# Motor_Driver.net
KiCad netlist of a schematic drawn in Altium Designer
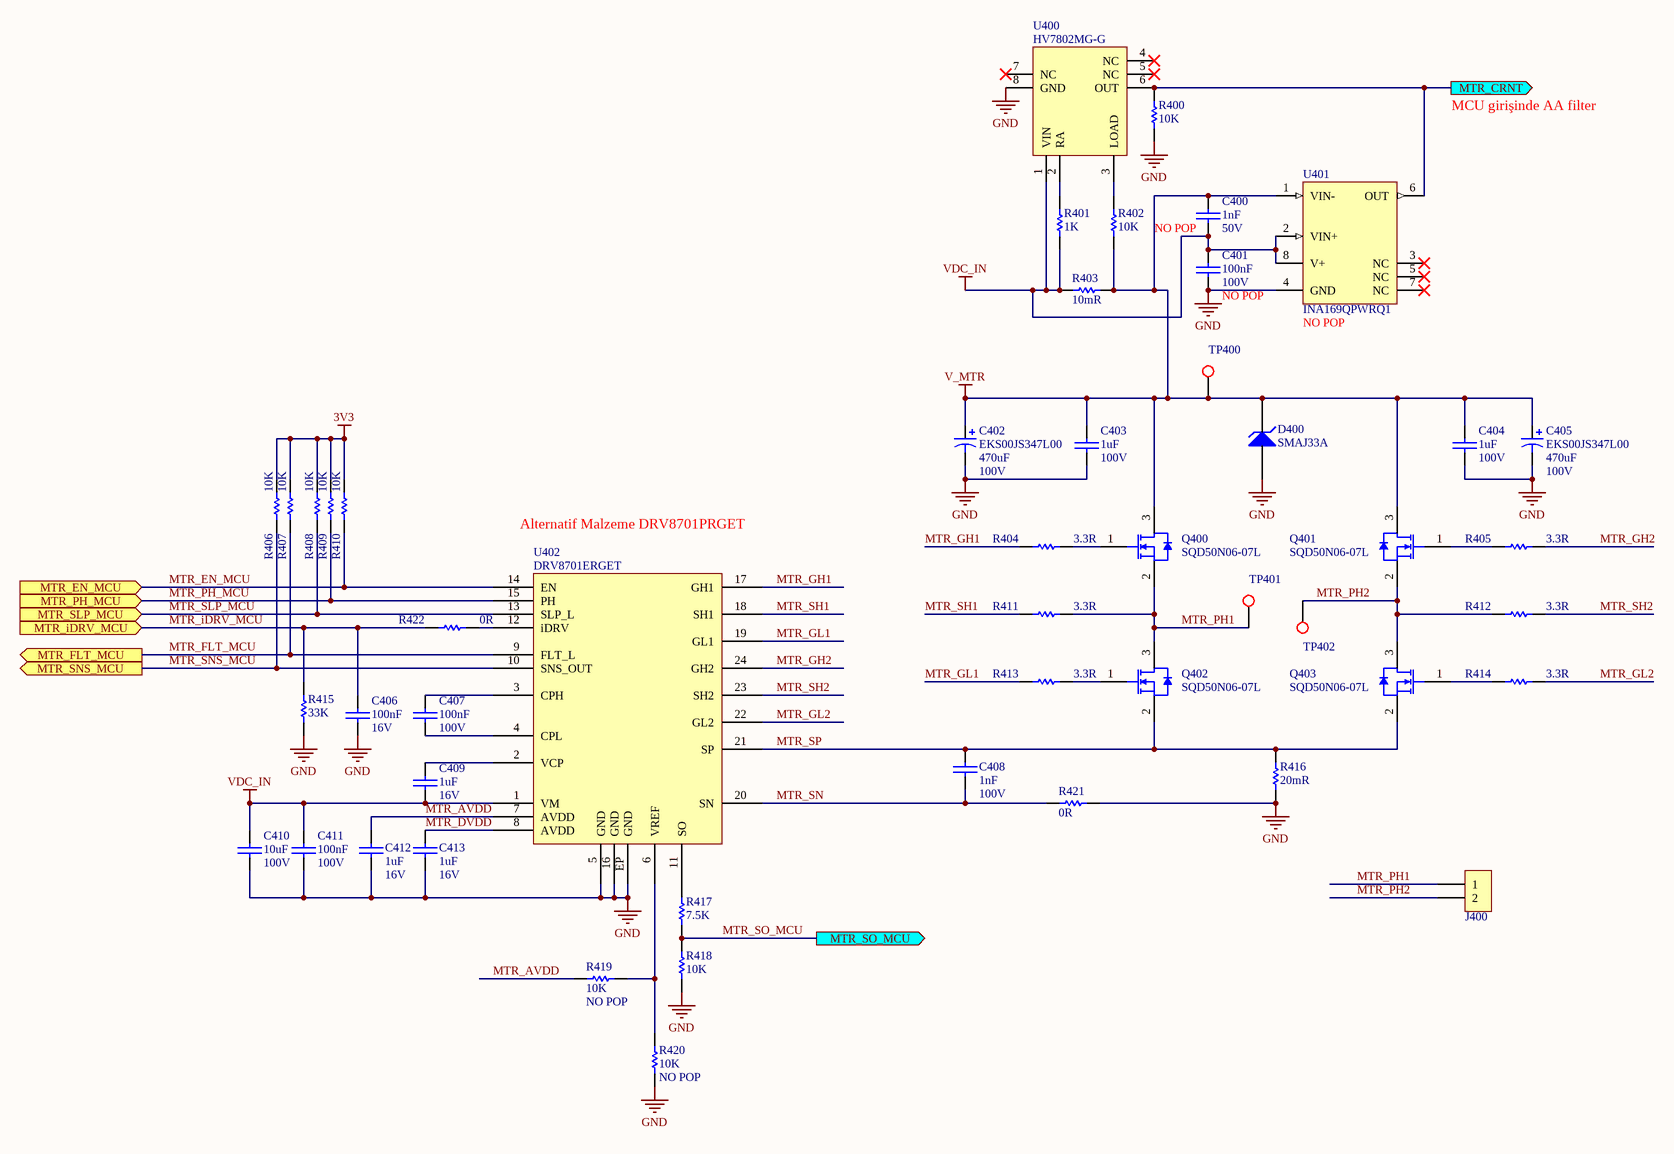
[diagram p0: Motor_Driver.SchDoc]

(export (version "E")
  (design (tool "Eeschema 10.0.6"))
  (components
    (comp (ref "C400")
      (value "1nF")
      (footprint "CAPC1005X06N")
      (description "CAP, CER, C0G, 1nF, %5, 50V, 0402")
      (fields
        (field (name "MANUFACTURER") "Murata")
        (field (name "MANUFACTURER PART NUMBER") "GRM1555C1H102JA01D")
        (field (name "OPERATING VOLTAGE") "50V")
        (field (name "ASSEMBLY") "NO POP")
      )
      (libsource (lib "Anime_Capacitor") (part "ACC0-0100-S272-0000"))
    )
    (comp (ref "C401")
      (value "100nF")
      (footprint "CAPC3216X09N")
      (description "CAP, CER, X7R, 100nF, %10, 100V, 1206")
      (fields
        (field (name "MANUFACTURER") "KEMET")
        (field (name "MANUFACTURER PART NUMBER") "C1206C104K1RACTU")
        (field (name "OPERATING VOLTAGE") "100V")
        (field (name "ASSEMBLY") "NO POP")
      )
      (libsource (lib "Anime_Capacitor") (part "ACC7-2100-S791-0000"))
    )
    (comp (ref "C402")
      (value "EKS00JS347L00")
      (footprint "CAPPR7.5-16X31.5")
      (description "Aluminum Electrolytic Capacitor, Radial Style with Long Leads: 470uF, 100V")
      (fields
        (field (name "ALTIUM_VALUE") "470uF")
        (field (name "RATED VOLTAGE") "100V")
        (field (name "PUBLISHER") "Altium Limited")
      )
      (libsource (lib "Vishay Roederstein Electrolytic Radial-Lead Capacitor") (part "EKS00JS347L00"))
    )
    (comp (ref "C403")
      (value "1uF")
      (footprint "CAPC3216X09N")
      (description "CAP, CER, X7R, 1uF, %10, 100V, 1206")
      (fields
        (field (name "MANUFACTURER") "Murata")
        (field (name "MANUFACTURER PART NUMBER") "GRM31CR72A105KA01L")
        (field (name "OPERATING VOLTAGE") "100V")
      )
      (libsource (lib "Anime_Capacitor") (part "ACC7-3100-S691-0000"))
    )
    (comp (ref "C404")
      (value "1uF")
      (footprint "CAPC3216X09N")
      (description "CAP, CER, X7R, 1uF, %10, 100V, 1206")
      (fields
        (field (name "MANUFACTURER") "Murata")
        (field (name "MANUFACTURER PART NUMBER") "GRM31CR72A105KA01L")
        (field (name "OPERATING VOLTAGE") "100V")
      )
      (libsource (lib "Anime_Capacitor") (part "ACC7-3100-S691-0000"))
    )
    (comp (ref "C405")
      (value "EKS00JS347L00")
      (footprint "CAPPR7.5-16X31.5")
      (description "Aluminum Electrolytic Capacitor, Radial Style with Long Leads: 470uF, 100V")
      (fields
        (field (name "ALTIUM_VALUE") "470uF")
        (field (name "RATED VOLTAGE") "100V")
        (field (name "PUBLISHER") "Altium Limited")
      )
      (libsource (lib "Vishay Roederstein Electrolytic Radial-Lead Capacitor") (part "EKS00JS347L00"))
    )
    (comp (ref "C406")
      (value "100nF")
      (footprint "CAPC1005X06N")
      (description "CAP, CER, X7R, 100nF, %10, 16V, 0402")
      (fields
        (field (name "MANUFACTURER") "Murata")
        (field (name "MANUFACTURER PART NUMBER") "GRM155R71C104KA88D")
        (field (name "OPERATING VOLTAGE") "16V")
      )
      (libsource (lib "Anime_Capacitor") (part "ACC7-2100-S241-0000"))
    )
    (comp (ref "C407")
      (value "100nF")
      (footprint "CAPC3216X09N")
      (description "CAP, CER, X7R, 100nF, %10, 100V, 1206")
      (fields
        (field (name "MANUFACTURER") "KEMET")
        (field (name "MANUFACTURER PART NUMBER") "C1206C104K1RACTU")
        (field (name "OPERATING VOLTAGE") "100V")
      )
      (libsource (lib "Anime_Capacitor") (part "ACC7-2100-S791-0000"))
    )
    (comp (ref "C408")
      (value "1nF")
      (footprint "CAPC1608X09N")
      (description "CAP, CER, X7R, 1nF, %10, 100V, 0603")
      (fields
        (field (name "MANUFACTURER") "Murata")
        (field (name "MANUFACTURER PART NUMBER") "GRM188R72A102KA01D")
        (field (name "OPERATING VOLTAGE") "100V")
      )
      (libsource (lib "Anime_Capacitor") (part "ACC7-0100-S391-0000"))
    )
    (comp (ref "C409")
      (value "1uF")
      (footprint "CAPC2012X14N")
      (description "CAP, CER, X7R, 1uF, %10, 16V, 0805")
      (fields
        (field (name "MANUFACTURER") "Murata")
        (field (name "MANUFACTURER PART NUMBER") "GRM21BR71C105KA01L")
        (field (name "OPERATING VOLTAGE") "16V")
      )
      (libsource (lib "Anime_Capacitor") (part "ACC7-3100-S441-0000"))
    )
    (comp (ref "C410")
      (value "10uF")
      (footprint "CAPC5750X25N")
      (description "CAP, CER, X7S, 10uF, %10, 100V, 2220")
      (fields
        (field (name "MANUFACTURER") "TDK")
        (field (name "MANUFACTURER PART NUMBER") "CGA9N3X7S2A106K230KB")
        (field (name "OPERATING VOLTAGE") "100V")
      )
      (libsource (lib "Anime_Capacitor") (part "ACC4-4100-SD91-0000"))
    )
    (comp (ref "C411")
      (value "100nF")
      (footprint "CAPC3216X09N")
      (description "CAP, CER, X7R, 100nF, %10, 100V, 1206")
      (fields
        (field (name "MANUFACTURER") "KEMET")
        (field (name "MANUFACTURER PART NUMBER") "C1206C104K1RACTU")
        (field (name "OPERATING VOLTAGE") "100V")
      )
      (libsource (lib "Anime_Capacitor") (part "ACC7-2100-S791-0000"))
    )
    (comp (ref "C412")
      (value "1uF")
      (footprint "CAPC2012X14N")
      (description "CAP, CER, X7R, 1uF, %10, 16V, 0805")
      (fields
        (field (name "MANUFACTURER") "Murata")
        (field (name "MANUFACTURER PART NUMBER") "GRM21BR71C105KA01L")
        (field (name "OPERATING VOLTAGE") "16V")
      )
      (libsource (lib "Anime_Capacitor") (part "ACC7-3100-S441-0000"))
    )
    (comp (ref "C413")
      (value "1uF")
      (footprint "CAPC2012X14N")
      (description "CAP, CER, X7R, 1uF, %10, 16V, 0805")
      (fields
        (field (name "MANUFACTURER") "Murata")
        (field (name "MANUFACTURER PART NUMBER") "GRM21BR71C105KA01L")
        (field (name "OPERATING VOLTAGE") "16V")
      )
      (libsource (lib "Anime_Capacitor") (part "ACC7-3100-S441-0000"))
    )
    (comp (ref "D400")
      (value "SMAJ33A")
      (footprint "DIOM5226X23N")
      (description "Diode, TVS, 3.5V @35A, 33V, 400W,  Uni-directional, DO-214AC")
      (fields (field (name "MANUFACTURER PART NUMBER") "SMAJ33A-13-F") (field (name "MANUFACTURER") "Diodes"))
      (libsource (lib "Anime_Semiconductor") (part "AS1H-975M-SI60-0001"))
    )
    (comp (ref "J400")
      (value "~")
      (footprint "AJ61-1002-TAPR-RNS0")
      (description "CON, Terminal, Klemens, 2 Pins, 1-Row, 5.08mm, TH, P, R")
      (fields
        (field (name "MANUFACTURER") "ON-SHORE")
        (field (name "MANUFACTURER PART NUMBER") "OSTOQ025451")
      )
      (libsource (lib "Anime_Connector") (part "AJ61-1002-TAPR-RNS0"))
    )
    (comp (ref "Q400")
      (value "SQD50N06-07L")
      (footprint "TO228P970-3N")
      (description "Transistor, MOSFET, N, 60V, 50A, 7.6mR, SQD50N06-07L, TO-252")
      (fields
        (field (name "MANUFACTURER PART NUMBER") "SQD50N06-07L-GE3")
        (field (name "MANUFACTURER") "VISHAY")
      )
      (libsource (lib "Anime_Semiconductor") (part "AS26-A50M-SI40-0000"))
    )
    (comp (ref "Q401")
      (value "SQD50N06-07L")
      (footprint "TO228P970-3N")
      (description "Transistor, MOSFET, N, 60V, 50A, 7.6mR, SQD50N06-07L, TO-252")
      (fields
        (field (name "MANUFACTURER PART NUMBER") "SQD50N06-07L-GE3")
        (field (name "MANUFACTURER") "VISHAY")
      )
      (libsource (lib "Anime_Semiconductor") (part "AS26-A50M-SI40-0000"))
    )
    (comp (ref "Q402")
      (value "SQD50N06-07L")
      (footprint "TO228P970-3N")
      (description "Transistor, MOSFET, N, 60V, 50A, 7.6mR, SQD50N06-07L, TO-252")
      (fields
        (field (name "MANUFACTURER PART NUMBER") "SQD50N06-07L-GE3")
        (field (name "MANUFACTURER") "VISHAY")
      )
      (libsource (lib "Anime_Semiconductor") (part "AS26-A50M-SI40-0000"))
    )
    (comp (ref "Q403")
      (value "SQD50N06-07L")
      (footprint "TO228P970-3N")
      (description "Transistor, MOSFET, N, 60V, 50A, 7.6mR, SQD50N06-07L, TO-252")
      (fields
        (field (name "MANUFACTURER PART NUMBER") "SQD50N06-07L-GE3")
        (field (name "MANUFACTURER") "VISHAY")
      )
      (libsource (lib "Anime_Semiconductor") (part "AS26-A50M-SI40-0000"))
    )
    (comp (ref "R400")
      (value "10K")
      (footprint "RESC1005X04N")
      (description "RES, E24, Thick Film, SMD, 10K, 1%, 0.1W, 0402")
      (fields
        (field (name "MANUFACTURER") "Panasonic")
        (field (name "MANUFACTURER PART NUMBER") "ERJ-2RKF1002X")
      )
      (libsource (lib "Anime_Resistor") (part "AR19-4100-S2B2-0000"))
    )
    (comp (ref "R401")
      (value "1K")
      (footprint "RESC1005X04N")
      (description "RES, E24, Thick Film, SMD, 1K, 1%, 0.1W, 0402")
      (fields
        (field (name "MANUFACTURER") "Panasonic")
        (field (name "MANUFACTURER PART NUMBER") "ERJ-2RKF1001X")
      )
      (libsource (lib "Anime_Resistor") (part "AR19-3100-S2B2-0000"))
    )
    (comp (ref "R402")
      (value "10K")
      (footprint "RESC1005X04N")
      (description "RES, E24, Thick Film, SMD, 10K, 1%, 0.1W, 0402")
      (fields
        (field (name "MANUFACTURER") "Panasonic")
        (field (name "MANUFACTURER PART NUMBER") "ERJ-2RKF1002X")
      )
      (libsource (lib "Anime_Resistor") (part "AR19-4100-S2B2-0000"))
    )
    (comp (ref "R403")
      (value "10mR")
      (footprint "RESC3216X08N")
      (description "RES, Thick Film, SMD, 10mR, 1%, 1W, 1206")
      (fields
        (field (name "MANUFACTURER") "Panasonic")
        (field (name "MANUFACTURER PART NUMBER") "ERJ-8BWFR010V")
      )
      (libsource (lib "Anime_Resistor") (part "AR19-Y100-S5D2-0000"))
    )
    (comp (ref "R404")
      (value "3.3R")
      (footprint "RESC2012X07N")
      (description "RES, E24, Thick Film, SMD, 3.3R, 1%, 0.125W, 0805")
      (fields
        (field (name "MANUFACTURER") "Panasonic")
        (field (name "MANUFACTURER PART NUMBER") "ERJ-6RQF3R3V")
      )
      (libsource (lib "Anime_Resistor") (part "AR19-0330-S4D2-0000"))
    )
    (comp (ref "R405")
      (value "3.3R")
      (footprint "RESC2012X07N")
      (description "RES, E24, Thick Film, SMD, 3.3R, 1%, 0.125W, 0805")
      (fields
        (field (name "MANUFACTURER") "Panasonic")
        (field (name "MANUFACTURER PART NUMBER") "ERJ-6RQF3R3V")
      )
      (libsource (lib "Anime_Resistor") (part "AR19-0330-S4D2-0000"))
    )
    (comp (ref "R406")
      (value "10K")
      (footprint "RESC1005X04N")
      (description "RES, E24, Thick Film, SMD, 10K, 1%, 0.1W, 0402")
      (fields
        (field (name "MANUFACTURER") "Panasonic")
        (field (name "MANUFACTURER PART NUMBER") "ERJ-2RKF1002X")
      )
      (libsource (lib "Anime_Resistor") (part "AR19-4100-S2B2-0000"))
    )
    (comp (ref "R407")
      (value "10K")
      (footprint "RESC1005X04N")
      (description "RES, E24, Thick Film, SMD, 10K, 1%, 0.1W, 0402")
      (fields
        (field (name "MANUFACTURER") "Panasonic")
        (field (name "MANUFACTURER PART NUMBER") "ERJ-2RKF1002X")
      )
      (libsource (lib "Anime_Resistor") (part "AR19-4100-S2B2-0000"))
    )
    (comp (ref "R408")
      (value "10K")
      (footprint "RESC1005X04N")
      (description "RES, E24, Thick Film, SMD, 10K, 1%, 0.1W, 0402")
      (fields
        (field (name "MANUFACTURER") "Panasonic")
        (field (name "MANUFACTURER PART NUMBER") "ERJ-2RKF1002X")
      )
      (libsource (lib "Anime_Resistor") (part "AR19-4100-S2B2-0000"))
    )
    (comp (ref "R409")
      (value "10K")
      (footprint "RESC1005X04N")
      (description "RES, E24, Thick Film, SMD, 10K, 1%, 0.1W, 0402")
      (fields
        (field (name "MANUFACTURER") "Panasonic")
        (field (name "MANUFACTURER PART NUMBER") "ERJ-2RKF1002X")
      )
      (libsource (lib "Anime_Resistor") (part "AR19-4100-S2B2-0000"))
    )
    (comp (ref "R410")
      (value "10K")
      (footprint "RESC1005X04N")
      (description "RES, E24, Thick Film, SMD, 10K, 1%, 0.1W, 0402")
      (fields
        (field (name "MANUFACTURER") "Panasonic")
        (field (name "MANUFACTURER PART NUMBER") "ERJ-2RKF1002X")
      )
      (libsource (lib "Anime_Resistor") (part "AR19-4100-S2B2-0000"))
    )
    (comp (ref "R411")
      (value "3.3R")
      (footprint "RESC2012X07N")
      (description "RES, E24, Thick Film, SMD, 3.3R, 1%, 0.125W, 0805")
      (fields
        (field (name "MANUFACTURER") "Panasonic")
        (field (name "MANUFACTURER PART NUMBER") "ERJ-6RQF3R3V")
      )
      (libsource (lib "Anime_Resistor") (part "AR19-0330-S4D2-0000"))
    )
    (comp (ref "R412")
      (value "3.3R")
      (footprint "RESC2012X07N")
      (description "RES, E24, Thick Film, SMD, 3.3R, 1%, 0.125W, 0805")
      (fields
        (field (name "MANUFACTURER") "Panasonic")
        (field (name "MANUFACTURER PART NUMBER") "ERJ-6RQF3R3V")
      )
      (libsource (lib "Anime_Resistor") (part "AR19-0330-S4D2-0000"))
    )
    (comp (ref "R413")
      (value "3.3R")
      (footprint "RESC2012X07N")
      (description "RES, E24, Thick Film, SMD, 3.3R, 1%, 0.125W, 0805")
      (fields
        (field (name "MANUFACTURER") "Panasonic")
        (field (name "MANUFACTURER PART NUMBER") "ERJ-6RQF3R3V")
      )
      (libsource (lib "Anime_Resistor") (part "AR19-0330-S4D2-0000"))
    )
    (comp (ref "R414")
      (value "3.3R")
      (footprint "RESC2012X07N")
      (description "RES, E24, Thick Film, SMD, 3.3R, 1%, 0.125W, 0805")
      (fields
        (field (name "MANUFACTURER") "Panasonic")
        (field (name "MANUFACTURER PART NUMBER") "ERJ-6RQF3R3V")
      )
      (libsource (lib "Anime_Resistor") (part "AR19-0330-S4D2-0000"))
    )
    (comp (ref "R415")
      (value "33K")
      (footprint "RESC1005X04N")
      (description "RES, E24, Thick Film, SMD, 33K, 1%, 0.1W, 0402")
      (fields
        (field (name "MANUFACTURER") "Panasonic")
        (field (name "MANUFACTURER PART NUMBER") "ERJ-2RKF3302X")
      )
      (libsource (lib "Anime_Resistor") (part "AR19-4330-S2B2-0000"))
    )
    (comp (ref "R416")
      (value "20mR")
      (footprint "RESC3216X08N")
      (description "RES, Thick Film, SMD, 20mR, 1%, 1W, 1206")
      (fields
        (field (name "MANUFACTURER") "Panasonic")
        (field (name "MANUFACTURER PART NUMBER") "ERJ-8BWFR020V")
      )
      (libsource (lib "Anime_Resistor") (part "AR19-Y200-S5D2-0000"))
    )
    (comp (ref "R417")
      (value "7.5K")
      (footprint "RESC1005X04N")
      (description "RES, E24, Thick Film, SMD, 7.5K, 1%, 0.1W, 0402")
      (fields
        (field (name "MANUFACTURER") "Panasonic")
        (field (name "MANUFACTURER PART NUMBER") "ERJ-2RKF7501X")
      )
      (libsource (lib "Anime_Resistor") (part "AR19-3750-S2B2-0000"))
    )
    (comp (ref "R418")
      (value "10K")
      (footprint "RESC1005X04N")
      (description "RES, E24, Thick Film, SMD, 10K, 1%, 0.1W, 0402")
      (fields
        (field (name "MANUFACTURER") "Panasonic")
        (field (name "MANUFACTURER PART NUMBER") "ERJ-2RKF1002X")
      )
      (libsource (lib "Anime_Resistor") (part "AR19-4100-S2B2-0000"))
    )
    (comp (ref "R419")
      (value "10K")
      (footprint "RESC1005X04N")
      (description "RES, E24, Thick Film, SMD, 10K, 1%, 0.1W, 0402")
      (fields
        (field (name "MANUFACTURER") "Panasonic")
        (field (name "MANUFACTURER PART NUMBER") "ERJ-2RKF1002X")
        (field (name "ASSEMBLY") "NO POP")
      )
      (libsource (lib "Anime_Resistor") (part "AR19-4100-S2B2-0000"))
    )
    (comp (ref "R420")
      (value "10K")
      (footprint "RESC1005X04N")
      (description "RES, E24, Thick Film, SMD, 10K, 1%, 0.1W, 0402")
      (fields
        (field (name "MANUFACTURER") "Panasonic")
        (field (name "MANUFACTURER PART NUMBER") "ERJ-2RKF1002X")
        (field (name "ASSEMBLY") "NO POP")
      )
      (libsource (lib "Anime_Resistor") (part "AR19-4100-S2B2-0000"))
    )
    (comp (ref "R421")
      (value "0R")
      (footprint "RESC2012X07N")
      (description "RES, Thick Film, SMD, 0R, Jumper, 0.125W, 0805")
      (fields
        (field (name "MANUFACTURER") "Panasonic")
        (field (name "MANUFACTURER PART NUMBER") "ERJ-6GEY0R00V")
      )
      (libsource (lib "Anime_Resistor") (part "AR19-0000-S407-0000"))
    )
    (comp (ref "R422")
      (value "0R")
      (footprint "RESC1005X04N")
      (description "RES, Thick Film, SMD, 0R, Jumper, 0.1W, 0402")
      (fields
        (field (name "MANUFACTURER") "Panasonic")
        (field (name "MANUFACTURER PART NUMBER") "ERJ-2GE0R00X")
      )
      (libsource (lib "Anime_Resistor") (part "AR19-0000-S201-0000"))
    )
    (comp (ref "TP400")
      (value "AEMT-C00S-1000-0000")
      (footprint "TP100")
      (description "Test Point, Circular, 1mm")
      (libsource (lib "Anime_Electromechanical") (part "AEMT-C00S-1000-0000"))
    )
    (comp (ref "TP401")
      (value "AEMT-C00S-1000-0000")
      (footprint "TP100")
      (description "Test Point, Circular, 1mm")
      (libsource (lib "Anime_Electromechanical") (part "AEMT-C00S-1000-0000"))
    )
    (comp (ref "TP402")
      (value "AEMT-C00S-1000-0000")
      (footprint "TP100")
      (description "Test Point, Circular, 1mm")
      (libsource (lib "Anime_Electromechanical") (part "AEMT-C00S-1000-0000"))
    )
    (comp (ref "U400")
      (value "HV7802MG-G")
      (footprint "MSOP65P490X110-8N")
      (description "IC, PMIC, Current Monitor, HV7802MG-G, MSOP-8")
      (fields (field (name "MANUFACTURER") "Microchip"))
      (libsource (lib "Anime_IC") (part "AT82-0000-SMC0-1860"))
    )
    (comp (ref "U401")
      (value "INA169QPWRQ1")
      (footprint "TSOP65P640X120-8N")
      (description "IC, PMIC, Current Monitor, INA169QPWRQ1, TSSOP-8")
      (fields (field (name "MANUFACTURER") "Texas Instruments") (field (name "ASSEMBLY") "NO POP"))
      (libsource (lib "Anime_IC") (part "AT82-0000-SM90-0690"))
    )
    (comp (ref "U402")
      (value "DRV8701ERGET")
      (footprint "QFN50P400X400X100_HS-25N")
      (description "IC, PMIC, Motor Driver, PWM Input, DRV8701ERGET, PQFN-24")
      (fields (field (name "MANUFACTURER") "Texas Instruments"))
      (libsource (lib "Anime_IC") (part "AT8B-0000-SF60-1850"))
    )
  )
  (nets
    (net (code "1") (name "/MTR_AVDD") (class "Default")
      (node (ref "C412") (pin "2") (pintype "passive"))
      (node (ref "R419") (pin "2") (pinfunction "2_2") (pintype "passive"))
      (node (ref "U402") (pin "7") (pinfunction "AVDD_7") (pintype "passive"))
    )
    (net (code "2") (name "/MTR_CRNT") (class "Default")
      (node (ref "R400") (pin "2") (pinfunction "2_2") (pintype "passive"))
      (node (ref "U400") (pin "6") (pinfunction "OUT_6") (pintype "passive"))
      (node (ref "U401") (pin "6") (pinfunction "OUT_6") (pintype "output"))
    )
    (net (code "3") (name "/MTR_DVDD") (class "Default")
      (node (ref "C413") (pin "2") (pintype "passive"))
      (node (ref "U402") (pin "8") (pinfunction "AVDD_8") (pintype "passive"))
    )
    (net (code "4") (name "/MTR_EN_MCU") (class "Default")
      (node (ref "R410") (pin "1") (pinfunction "1_1") (pintype "passive"))
      (node (ref "U402") (pin "14") (pinfunction "EN_14") (pintype "passive"))
    )
    (net (code "5") (name "/MTR_FLT_MCU") (class "Default")
      (node (ref "R407") (pin "1") (pinfunction "1_1") (pintype "passive"))
      (node (ref "U402") (pin "9") (pinfunction "FLT_L_9") (pintype "passive"))
    )
    (net (code "6") (name "/MTR_GH1") (class "Default")
      (node (ref "R404") (pin "1") (pinfunction "1_1") (pintype "passive"))
      (node (ref "U402") (pin "17") (pinfunction "GH1_17") (pintype "passive"))
    )
    (net (code "7") (name "/MTR_GH2") (class "Default")
      (node (ref "R405") (pin "2") (pinfunction "2_2") (pintype "passive"))
      (node (ref "U402") (pin "24") (pinfunction "GH2_24") (pintype "passive"))
    )
    (net (code "8") (name "/MTR_GL1") (class "Default")
      (node (ref "R413") (pin "1") (pinfunction "1_1") (pintype "passive"))
      (node (ref "U402") (pin "19") (pinfunction "GL1_19") (pintype "passive"))
    )
    (net (code "9") (name "/MTR_GL2") (class "Default")
      (node (ref "R414") (pin "2") (pinfunction "2_2") (pintype "passive"))
      (node (ref "U402") (pin "22") (pinfunction "GL2_22") (pintype "passive"))
    )
    (net (code "10") (name "/MTR_PH1") (class "Default")
      (node (ref "J400") (pin "1") (pinfunction "1_1") (pintype "passive"))
      (node (ref "Q400") (pin "2") (pinfunction "Source_2") (pintype "passive"))
      (node (ref "Q402") (pin "3") (pinfunction "Drain_3") (pintype "passive"))
      (node (ref "R411") (pin "2") (pinfunction "2_2") (pintype "passive"))
      (node (ref "TP401") (pin "1") (pintype "passive"))
    )
    (net (code "11") (name "/MTR_PH2") (class "Default")
      (node (ref "J400") (pin "2") (pinfunction "2_2") (pintype "passive"))
      (node (ref "Q401") (pin "2") (pinfunction "Source_2") (pintype "passive"))
      (node (ref "Q403") (pin "3") (pinfunction "Drain_3") (pintype "passive"))
      (node (ref "R412") (pin "1") (pinfunction "1_1") (pintype "passive"))
      (node (ref "TP402") (pin "1") (pintype "passive"))
    )
    (net (code "12") (name "/MTR_PH_MCU") (class "Default")
      (node (ref "R409") (pin "1") (pinfunction "1_1") (pintype "passive"))
      (node (ref "U402") (pin "15") (pinfunction "PH_15") (pintype "passive"))
    )
    (net (code "13") (name "/MTR_SH1") (class "Default")
      (node (ref "R411") (pin "1") (pinfunction "1_1") (pintype "passive"))
      (node (ref "U402") (pin "18") (pinfunction "SH1_18") (pintype "passive"))
    )
    (net (code "14") (name "/MTR_SH2") (class "Default")
      (node (ref "R412") (pin "2") (pinfunction "2_2") (pintype "passive"))
      (node (ref "U402") (pin "23") (pinfunction "SH2_23") (pintype "passive"))
    )
    (net (code "15") (name "/MTR_SLP_MCU") (class "Default")
      (node (ref "R408") (pin "1") (pinfunction "1_1") (pintype "passive"))
      (node (ref "U402") (pin "13") (pinfunction "SLP_L_13") (pintype "passive"))
    )
    (net (code "16") (name "/MTR_SN") (class "Default")
      (node (ref "C408") (pin "1") (pintype "passive"))
      (node (ref "R421") (pin "1") (pinfunction "1_1") (pintype "passive"))
      (node (ref "U402") (pin "20") (pinfunction "SN_20") (pintype "passive"))
    )
    (net (code "17") (name "/MTR_SNS_MCU") (class "Default")
      (node (ref "R406") (pin "1") (pinfunction "1_1") (pintype "passive"))
      (node (ref "U402") (pin "10") (pinfunction "SNS_OUT_10") (pintype "passive"))
    )
    (net (code "18") (name "/MTR_SO_MCU") (class "Default")
      (node (ref "R417") (pin "1") (pinfunction "1_1") (pintype "passive"))
      (node (ref "R418") (pin "1") (pinfunction "1_1") (pintype "passive"))
    )
    (net (code "19") (name "/MTR_SP") (class "Default")
      (node (ref "C408") (pin "2") (pintype "passive"))
      (node (ref "Q402") (pin "2") (pinfunction "Source_2") (pintype "passive"))
      (node (ref "Q403") (pin "2") (pinfunction "Source_2") (pintype "passive"))
      (node (ref "R416") (pin "2") (pinfunction "2_2") (pintype "passive"))
      (node (ref "U402") (pin "21") (pinfunction "SP_21") (pintype "passive"))
    )
    (net (code "20") (name "/MTR_iDRV_MCU") (class "Default")
      (node (ref "C406") (pin "2") (pintype "passive"))
      (node (ref "R415") (pin "2") (pinfunction "2_2") (pintype "passive"))
      (node (ref "R422") (pin "1") (pinfunction "1_1") (pintype "passive"))
    )
    (net (code "21") (name "3V3") (class "Default")
      (node (ref "R406") (pin "2") (pinfunction "2_2") (pintype "passive"))
      (node (ref "R407") (pin "2") (pinfunction "2_2") (pintype "passive"))
      (node (ref "R408") (pin "2") (pinfunction "2_2") (pintype "passive"))
      (node (ref "R409") (pin "2") (pinfunction "2_2") (pintype "passive"))
      (node (ref "R410") (pin "2") (pinfunction "2_2") (pintype "passive"))
    )
    (net (code "22") (name "GND") (class "Default")
      (node (ref "C401") (pin "1") (pintype "passive"))
      (node (ref "C402") (pin "2") (pinfunction "2_2") (pintype "passive"))
      (node (ref "C403") (pin "1") (pintype "passive"))
      (node (ref "C404") (pin "1") (pintype "passive"))
      (node (ref "C405") (pin "2") (pinfunction "2_2") (pintype "passive"))
      (node (ref "C406") (pin "1") (pintype "passive"))
      (node (ref "C410") (pin "1") (pintype "passive"))
      (node (ref "C411") (pin "1") (pintype "passive"))
      (node (ref "C412") (pin "1") (pintype "passive"))
      (node (ref "C413") (pin "1") (pintype "passive"))
      (node (ref "D400") (pin "2") (pinfunction "A_2") (pintype "passive"))
      (node (ref "R400") (pin "1") (pinfunction "1_1") (pintype "passive"))
      (node (ref "R415") (pin "1") (pinfunction "1_1") (pintype "passive"))
      (node (ref "R416") (pin "1") (pinfunction "1_1") (pintype "passive"))
      (node (ref "R418") (pin "2") (pinfunction "2_2") (pintype "passive"))
      (node (ref "R420") (pin "1") (pinfunction "1_1") (pintype "passive"))
      (node (ref "R421") (pin "2") (pinfunction "2_2") (pintype "passive"))
      (node (ref "U400") (pin "8") (pinfunction "GND_8") (pintype "power_in"))
      (node (ref "U401") (pin "4") (pinfunction "GND_4") (pintype "power_in"))
      (node (ref "U402") (pin "16") (pinfunction "GND_16") (pintype "power_in"))
      (node (ref "U402") (pin "5") (pinfunction "GND_5") (pintype "power_in"))
      (node (ref "U402") (pin "EP") (pinfunction "GND_EP") (pintype "power_in"))
    )
    (net (code "23") (name "Net-(Q400-Gate)") (class "Default")
      (node (ref "Q400") (pin "1") (pinfunction "Gate_1") (pintype "passive"))
      (node (ref "R404") (pin "2") (pinfunction "2_2") (pintype "passive"))
    )
    (net (code "24") (name "Net-(Q401-Gate)") (class "Default")
      (node (ref "Q401") (pin "1") (pinfunction "Gate_1") (pintype "passive"))
      (node (ref "R405") (pin "1") (pinfunction "1_1") (pintype "passive"))
    )
    (net (code "25") (name "Net-(Q402-Gate)") (class "Default")
      (node (ref "Q402") (pin "1") (pinfunction "Gate_1") (pintype "passive"))
      (node (ref "R413") (pin "2") (pinfunction "2_2") (pintype "passive"))
    )
    (net (code "26") (name "Net-(Q403-Gate)") (class "Default")
      (node (ref "Q403") (pin "1") (pinfunction "Gate_1") (pintype "passive"))
      (node (ref "R414") (pin "1") (pinfunction "1_1") (pintype "passive"))
    )
    (net (code "27") (name "Net-(U400-LOAD)") (class "Default")
      (node (ref "R402") (pin "2") (pinfunction "2_2") (pintype "passive"))
      (node (ref "U400") (pin "3") (pinfunction "LOAD_3") (pintype "passive"))
    )
    (net (code "28") (name "Net-(U400-RA)") (class "Default")
      (node (ref "R401") (pin "2") (pinfunction "2_2") (pintype "passive"))
      (node (ref "U400") (pin "2") (pinfunction "RA_2") (pintype "passive"))
    )
    (net (code "29") (name "Net-(U402-CPH)") (class "Default")
      (node (ref "C407") (pin "2") (pintype "passive"))
      (node (ref "U402") (pin "3") (pinfunction "CPH_3") (pintype "passive"))
    )
    (net (code "30") (name "Net-(U402-CPL)") (class "Default")
      (node (ref "C407") (pin "1") (pintype "passive"))
      (node (ref "U402") (pin "4") (pinfunction "CPL_4") (pintype "passive"))
    )
    (net (code "31") (name "Net-(U402-SO)") (class "Default")
      (node (ref "R417") (pin "2") (pinfunction "2_2") (pintype "passive"))
      (node (ref "U402") (pin "11") (pinfunction "SO_11") (pintype "passive"))
    )
    (net (code "32") (name "Net-(U402-VCP)") (class "Default")
      (node (ref "C409") (pin "2") (pintype "passive"))
      (node (ref "U402") (pin "2") (pinfunction "VCP_2") (pintype "passive"))
    )
    (net (code "33") (name "Net-(U402-VREF)") (class "Default")
      (node (ref "R419") (pin "1") (pinfunction "1_1") (pintype "passive"))
      (node (ref "R420") (pin "2") (pinfunction "2_2") (pintype "passive"))
      (node (ref "U402") (pin "6") (pinfunction "VREF_6") (pintype "power_in"))
    )
    (net (code "34") (name "Net-(U402-iDRV)") (class "Default")
      (node (ref "R422") (pin "2") (pinfunction "2_2") (pintype "passive"))
      (node (ref "U402") (pin "12") (pinfunction "iDRV_12") (pintype "passive"))
    )
    (net (code "35") (name "VDC_IN") (class "Default")
      (node (ref "C400") (pin "1") (pintype "passive"))
      (node (ref "C401") (pin "2") (pintype "passive"))
      (node (ref "C409") (pin "1") (pintype "passive"))
      (node (ref "C410") (pin "2") (pintype "passive"))
      (node (ref "C411") (pin "2") (pintype "passive"))
      (node (ref "R401") (pin "1") (pinfunction "1_1") (pintype "passive"))
      (node (ref "R403") (pin "1") (pinfunction "1_1") (pintype "passive"))
      (node (ref "U400") (pin "1") (pinfunction "VIN_1") (pintype "passive"))
      (node (ref "U401") (pin "2") (pinfunction "VIN+_2") (pintype "input"))
      (node (ref "U401") (pin "8") (pinfunction "V+_8") (pintype "power_in"))
      (node (ref "U402") (pin "1") (pinfunction "VM_1") (pintype "passive"))
    )
    (net (code "36") (name "V_MTR") (class "Default")
      (node (ref "C400") (pin "2") (pintype "passive"))
      (node (ref "C402") (pin "1") (pinfunction "1_1") (pintype "passive"))
      (node (ref "C403") (pin "2") (pintype "passive"))
      (node (ref "C404") (pin "2") (pintype "passive"))
      (node (ref "C405") (pin "1") (pinfunction "1_1") (pintype "passive"))
      (node (ref "D400") (pin "1") (pinfunction "K_1") (pintype "passive"))
      (node (ref "Q400") (pin "3") (pinfunction "Drain_3") (pintype "passive"))
      (node (ref "Q401") (pin "3") (pinfunction "Drain_3") (pintype "passive"))
      (node (ref "R402") (pin "1") (pinfunction "1_1") (pintype "passive"))
      (node (ref "R403") (pin "2") (pinfunction "2_2") (pintype "passive"))
      (node (ref "TP400") (pin "1") (pintype "passive"))
      (node (ref "U401") (pin "1") (pinfunction "VIN-_1") (pintype "input"))
    )
    (net (code "37") (name "unconnected-(U400-NC-Pad4)") (class "Default")
      (node (ref "U400") (pin "4") (pinfunction "NC_4") (pintype "passive+no_connect"))
    )
    (net (code "38") (name "unconnected-(U400-NC-Pad5)") (class "Default")
      (node (ref "U400") (pin "5") (pinfunction "NC_5") (pintype "passive+no_connect"))
    )
    (net (code "39") (name "unconnected-(U400-NC-Pad7)") (class "Default")
      (node (ref "U400") (pin "7") (pinfunction "NC_7") (pintype "passive+no_connect"))
    )
    (net (code "40") (name "unconnected-(U401-NC-Pad3)") (class "Default")
      (node (ref "U401") (pin "3") (pinfunction "NC_3") (pintype "passive+no_connect"))
    )
    (net (code "41") (name "unconnected-(U401-NC-Pad5)") (class "Default")
      (node (ref "U401") (pin "5") (pinfunction "NC_5") (pintype "passive+no_connect"))
    )
    (net (code "42") (name "unconnected-(U401-NC-Pad7)") (class "Default")
      (node (ref "U401") (pin "7") (pinfunction "NC_7") (pintype "passive+no_connect"))
    )
  )
)
